# M705J.net
KiCad netlist of a schematic drawn in EAGLE
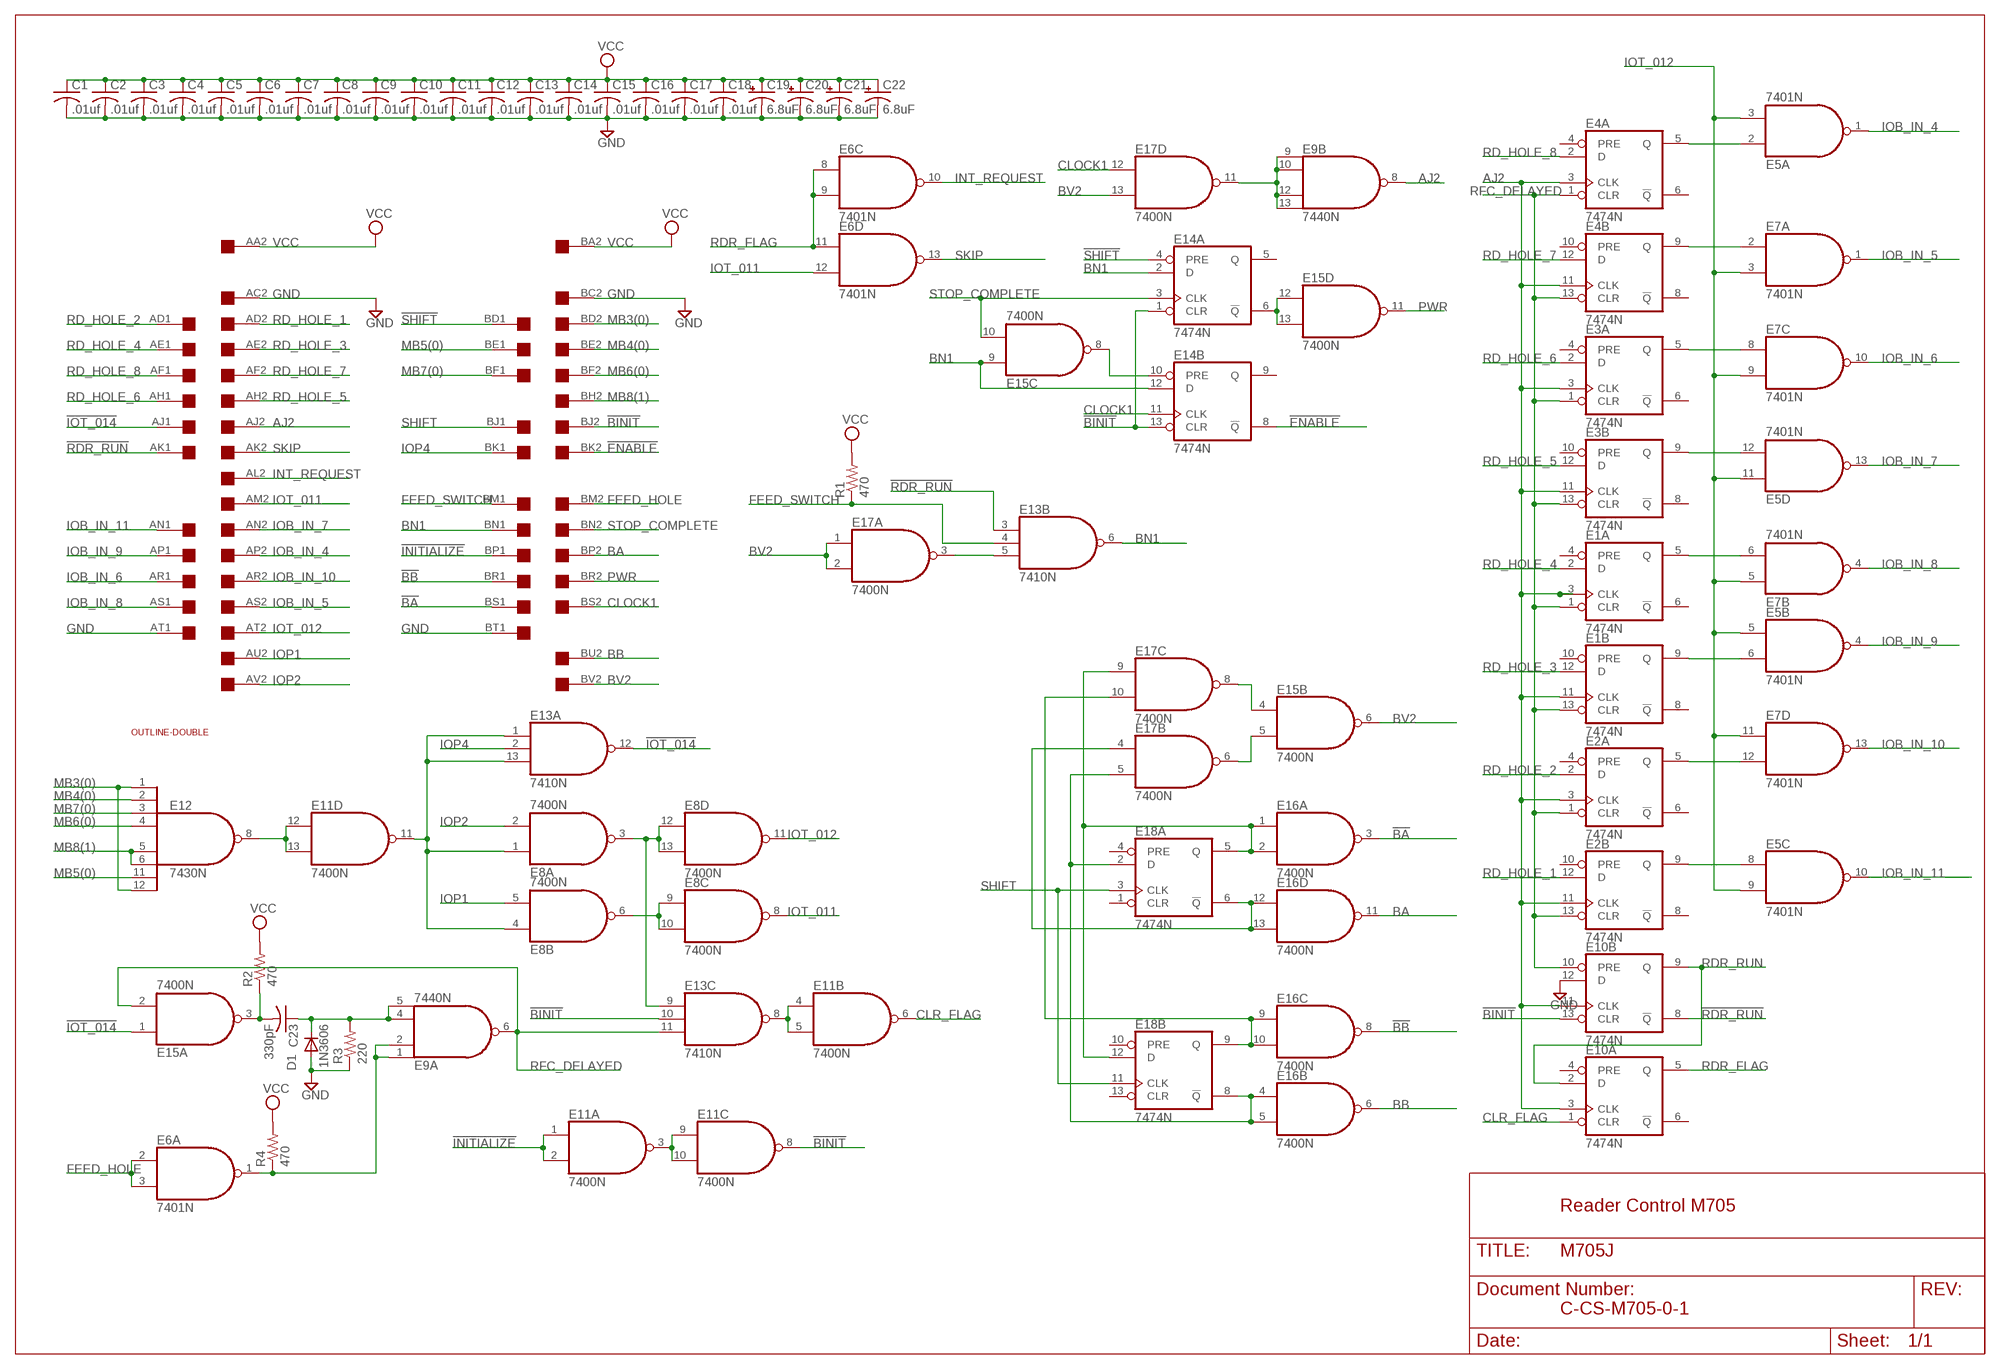
[diagram p0: schematic, sheet 1]

(export (version "E")
  (design (tool "Eeschema 10.0.6"))
  (components
    (comp (ref "C1")
      (value ".01uf")
      (footprint "eagle-import:C075-032X103")
      (libsource (lib "eagle-import") (part "C-US075-032X103"))
    )
    (comp (ref "C2")
      (value ".01uf")
      (footprint "eagle-import:C075-032X103")
      (libsource (lib "eagle-import") (part "C-US075-032X103"))
    )
    (comp (ref "C3")
      (value ".01uf")
      (footprint "eagle-import:C075-032X103")
      (libsource (lib "eagle-import") (part "C-US075-032X103"))
    )
    (comp (ref "C4")
      (value ".01uf")
      (footprint "eagle-import:C075-032X103")
      (libsource (lib "eagle-import") (part "C-US075-032X103"))
    )
    (comp (ref "C5")
      (value ".01uf")
      (footprint "eagle-import:C075-032X103")
      (libsource (lib "eagle-import") (part "C-US075-032X103"))
    )
    (comp (ref "C6")
      (value ".01uf")
      (footprint "eagle-import:C075-032X103")
      (libsource (lib "eagle-import") (part "C-US075-032X103"))
    )
    (comp (ref "C7")
      (value ".01uf")
      (footprint "eagle-import:C075-032X103")
      (libsource (lib "eagle-import") (part "C-US075-032X103"))
    )
    (comp (ref "C8")
      (value ".01uf")
      (footprint "eagle-import:C075-032X103")
      (libsource (lib "eagle-import") (part "C-US075-032X103"))
    )
    (comp (ref "C9")
      (value ".01uf")
      (footprint "eagle-import:C075-032X103")
      (libsource (lib "eagle-import") (part "C-US075-032X103"))
    )
    (comp (ref "C10")
      (value ".01uf")
      (footprint "eagle-import:C075-032X103")
      (libsource (lib "eagle-import") (part "C-US075-032X103"))
    )
    (comp (ref "C11")
      (value ".01uf")
      (footprint "eagle-import:C075-032X103")
      (libsource (lib "eagle-import") (part "C-US075-032X103"))
    )
    (comp (ref "C12")
      (value ".01uf")
      (footprint "eagle-import:C075-032X103")
      (libsource (lib "eagle-import") (part "C-US075-032X103"))
    )
    (comp (ref "C13")
      (value ".01uf")
      (footprint "eagle-import:C075-032X103")
      (libsource (lib "eagle-import") (part "C-US075-032X103"))
    )
    (comp (ref "C14")
      (value ".01uf")
      (footprint "eagle-import:C075-032X103")
      (libsource (lib "eagle-import") (part "C-US075-032X103"))
    )
    (comp (ref "C15")
      (value ".01uf")
      (footprint "eagle-import:C075-032X103")
      (libsource (lib "eagle-import") (part "C-US075-032X103"))
    )
    (comp (ref "C16")
      (value ".01uf")
      (footprint "eagle-import:C075-032X103")
      (libsource (lib "eagle-import") (part "C-US075-032X103"))
    )
    (comp (ref "C17")
      (value ".01uf")
      (footprint "eagle-import:C075-032X103")
      (libsource (lib "eagle-import") (part "C-US075-032X103"))
    )
    (comp (ref "C18")
      (value ".01uf")
      (footprint "eagle-import:C075-032X103")
      (libsource (lib "eagle-import") (part "C-US075-032X103"))
    )
    (comp (ref "C19")
      (value "6.8uF")
      (footprint "eagle-import:E12-8")
      (libsource (lib "eagle-import") (part "CPOL-USE20-8AXIAL"))
    )
    (comp (ref "C20")
      (value "6.8uF")
      (footprint "eagle-import:E12-8")
      (libsource (lib "eagle-import") (part "CPOL-USE20-8AXIAL"))
    )
    (comp (ref "C21")
      (value "6.8uF")
      (footprint "eagle-import:E12-8")
      (libsource (lib "eagle-import") (part "CPOL-USE20-8AXIAL"))
    )
    (comp (ref "C22")
      (value "6.8uF")
      (footprint "eagle-import:E12-8")
      (libsource (lib "eagle-import") (part "CPOL-USE20-8AXIAL"))
    )
    (comp (ref "C23")
      (value "330pF")
      (footprint "eagle-import:C075-032X103")
      (libsource (lib "eagle-import") (part "C-US075-032X103"))
    )
    (comp (ref "D1")
      (value "1N3606")
      (footprint "eagle-import:DO35-10")
      (libsource (lib "eagle-import") (part "1N4148DO35-10"))
    )
    (comp (ref "E1")
      (value "7474N")
      (footprint "eagle-import:DIL14")
      (libsource (lib "eagle-import") (part "7474NS"))
    )
    (comp (ref "E2")
      (value "7474N")
      (footprint "eagle-import:DIL14")
      (libsource (lib "eagle-import") (part "7474NS"))
    )
    (comp (ref "E3")
      (value "7474N")
      (footprint "eagle-import:DIL14")
      (libsource (lib "eagle-import") (part "7474NS"))
    )
    (comp (ref "E4")
      (value "7474N")
      (footprint "eagle-import:DIL14")
      (libsource (lib "eagle-import") (part "7474NS"))
    )
    (comp (ref "E5")
      (value "7401N")
      (footprint "eagle-import:DIL14")
      (libsource (lib "eagle-import") (part "7401NLS"))
    )
    (comp (ref "E6")
      (value "7401N")
      (footprint "eagle-import:DIL14")
      (libsource (lib "eagle-import") (part "7401NLS"))
    )
    (comp (ref "E7")
      (value "7401N")
      (footprint "eagle-import:DIL14")
      (libsource (lib "eagle-import") (part "7401NLS"))
    )
    (comp (ref "E8")
      (value "7400N")
      (footprint "eagle-import:DIL14")
      (libsource (lib "eagle-import") (part "7400N"))
    )
    (comp (ref "E9")
      (value "7440N")
      (footprint "eagle-import:DIL14")
      (libsource (lib "eagle-import") (part "7420NS"))
    )
    (comp (ref "E10")
      (value "7474N")
      (footprint "eagle-import:DIL14")
      (libsource (lib "eagle-import") (part "7474NS"))
    )
    (comp (ref "E11")
      (value "7400N")
      (footprint "eagle-import:DIL14")
      (libsource (lib "eagle-import") (part "7400N"))
    )
    (comp (ref "E12")
      (value "7430N")
      (footprint "eagle-import:DIL14")
      (libsource (lib "eagle-import") (part "7430N"))
    )
    (comp (ref "E13")
      (value "7410N")
      (footprint "eagle-import:DIL14")
      (libsource (lib "eagle-import") (part "7410N"))
    )
    (comp (ref "E14")
      (value "7474N")
      (footprint "eagle-import:DIL14")
      (libsource (lib "eagle-import") (part "7474NS"))
    )
    (comp (ref "E15")
      (value "7400N")
      (footprint "eagle-import:DIL14")
      (libsource (lib "eagle-import") (part "7400N"))
    )
    (comp (ref "E16")
      (value "7400N")
      (footprint "eagle-import:DIL14")
      (libsource (lib "eagle-import") (part "7400N"))
    )
    (comp (ref "E17")
      (value "7400N")
      (footprint "eagle-import:DIL14")
      (libsource (lib "eagle-import") (part "7400N"))
    )
    (comp (ref "E18")
      (value "7474N")
      (footprint "eagle-import:DIL14")
      (libsource (lib "eagle-import") (part "7474NS"))
    )
    (comp (ref "R1")
      (value "470")
      (footprint "eagle-import:0207_10")
      (libsource (lib "eagle-import") (part "R-US_0207/10"))
    )
    (comp (ref "R2")
      (value "470")
      (footprint "eagle-import:0207_10")
      (libsource (lib "eagle-import") (part "R-US_0207/10"))
    )
    (comp (ref "R3")
      (value "220")
      (footprint "eagle-import:0207_10")
      (libsource (lib "eagle-import") (part "R-US_0207/10"))
    )
    (comp (ref "R4")
      (value "470")
      (footprint "eagle-import:0207_10")
      (libsource (lib "eagle-import") (part "R-US_0207/10"))
    )
    (comp (ref "U$5")
      (value "DOUBLE")
      (footprint "eagle-import:EDGE-CON4")
      (libsource (lib "eagle-import") (part "DOUBLE"))
    )
    (comp (ref "U$6")
      (value "OUTLINE-DOUBLE")
      (footprint "eagle-import:DOUBLE")
      (libsource (lib "eagle-import") (part "OUTLINE-DOUBLE"))
    )
  )
  (nets
    (net (code "1") (name "/AJ2") (class "Default")
      (node (ref "E1") (pin "11") (pinfunction "CLK_11") (pintype "input"))
      (node (ref "E1") (pin "3") (pinfunction "CLK_3") (pintype "input"))
      (node (ref "E10") (pin "11") (pinfunction "CLK_11") (pintype "input"))
      (node (ref "E10") (pin "3") (pinfunction "CLK_3") (pintype "input"))
      (node (ref "E2") (pin "11") (pinfunction "CLK_11") (pintype "input"))
      (node (ref "E2") (pin "3") (pinfunction "CLK_3") (pintype "input"))
      (node (ref "E3") (pin "11") (pinfunction "CLK_11") (pintype "input"))
      (node (ref "E3") (pin "3") (pinfunction "CLK_3") (pintype "input"))
      (node (ref "E4") (pin "11") (pinfunction "CLK_11") (pintype "input"))
      (node (ref "E4") (pin "3") (pinfunction "CLK_3") (pintype "input"))
      (node (ref "E9") (pin "8") (pinfunction "O_8") (pintype "output"))
      (node (ref "U$5") (pin "AJ2") (pinfunction "1_AJ2") (pintype "bidirectional"))
    )
    (net (code "2") (name "/BA") (class "Default")
      (node (ref "E16") (pin "11") (pinfunction "O_11") (pintype "output"))
      (node (ref "U$5") (pin "BP2") (pinfunction "1_BP2") (pintype "bidirectional"))
    )
    (net (code "3") (name "/BB") (class "Default")
      (node (ref "E16") (pin "6") (pinfunction "O_6") (pintype "output"))
      (node (ref "U$5") (pin "BU2") (pinfunction "1_BU2") (pintype "bidirectional"))
    )
    (net (code "4") (name "/BN1") (class "Default")
      (node (ref "E13") (pin "6") (pinfunction "O_6") (pintype "output"))
      (node (ref "E14") (pin "12") (pinfunction "D_12") (pintype "input"))
      (node (ref "E14") (pin "2") (pinfunction "D_2") (pintype "input"))
      (node (ref "E15") (pin "9") (pinfunction "I0_9") (pintype "input"))
      (node (ref "U$5") (pin "BN1") (pinfunction "1_BN1") (pintype "bidirectional"))
    )
    (net (code "5") (name "/BV2") (class "Default")
      (node (ref "E15") (pin "6") (pinfunction "O_6") (pintype "output"))
      (node (ref "E17") (pin "1") (pinfunction "I0_1") (pintype "input"))
      (node (ref "E17") (pin "13") (pinfunction "I1_13") (pintype "input"))
      (node (ref "E17") (pin "2") (pinfunction "I1_2") (pintype "input"))
      (node (ref "U$5") (pin "BV2") (pinfunction "1_BV2") (pintype "bidirectional"))
    )
    (net (code "6") (name "/CLOCK1") (class "Default")
      (node (ref "E14") (pin "11") (pinfunction "CLK_11") (pintype "input"))
      (node (ref "E17") (pin "12") (pinfunction "I0_12") (pintype "input"))
      (node (ref "U$5") (pin "BS2") (pinfunction "1_BS2") (pintype "bidirectional"))
    )
    (net (code "7") (name "/CLR_FLAG") (class "Default")
      (node (ref "E10") (pin "1") (pinfunction "CLR_1") (pintype "input"))
      (node (ref "E11") (pin "6") (pinfunction "O_6") (pintype "output"))
    )
    (net (code "8") (name "/FEED_HOLE") (class "Default")
      (node (ref "E6") (pin "2") (pinfunction "I0_2") (pintype "input"))
      (node (ref "E6") (pin "3") (pinfunction "I1_3") (pintype "input"))
      (node (ref "U$5") (pin "BM2") (pinfunction "1_BM2") (pintype "bidirectional"))
    )
    (net (code "9") (name "/FEED_SWITCH") (class "Default")
      (node (ref "E13") (pin "4") (pinfunction "I1_4") (pintype "input"))
      (node (ref "R1") (pin "1") (pinfunction "1_1") (pintype "passive"))
      (node (ref "U$5") (pin "BM1") (pinfunction "1_BM1") (pintype "bidirectional"))
    )
    (net (code "10") (name "/INT_REQUEST") (class "Default")
      (node (ref "E6") (pin "10") (pinfunction "O_10") (pintype "open_collector"))
      (node (ref "U$5") (pin "AL2") (pinfunction "1_AL2") (pintype "bidirectional"))
    )
    (net (code "11") (name "/IOB_IN_4") (class "Default")
      (node (ref "E5") (pin "1") (pinfunction "O_1") (pintype "open_collector"))
      (node (ref "U$5") (pin "AP2") (pinfunction "1_AP2") (pintype "bidirectional"))
    )
    (net (code "12") (name "/IOB_IN_5") (class "Default")
      (node (ref "E7") (pin "1") (pinfunction "O_1") (pintype "open_collector"))
      (node (ref "U$5") (pin "AS2") (pinfunction "1_AS2") (pintype "bidirectional"))
    )
    (net (code "13") (name "/IOB_IN_6") (class "Default")
      (node (ref "E7") (pin "10") (pinfunction "O_10") (pintype "open_collector"))
      (node (ref "U$5") (pin "AR1") (pinfunction "1_AR1") (pintype "bidirectional"))
    )
    (net (code "14") (name "/IOB_IN_7") (class "Default")
      (node (ref "E5") (pin "13") (pinfunction "O_13") (pintype "open_collector"))
      (node (ref "U$5") (pin "AN2") (pinfunction "1_AN2") (pintype "bidirectional"))
    )
    (net (code "15") (name "/IOB_IN_8") (class "Default")
      (node (ref "E7") (pin "4") (pinfunction "O_4") (pintype "open_collector"))
      (node (ref "U$5") (pin "AS1") (pinfunction "1_AS1") (pintype "bidirectional"))
    )
    (net (code "16") (name "/IOB_IN_9") (class "Default")
      (node (ref "E5") (pin "4") (pinfunction "O_4") (pintype "open_collector"))
      (node (ref "U$5") (pin "AP1") (pinfunction "1_AP1") (pintype "bidirectional"))
    )
    (net (code "17") (name "/IOB_IN_10") (class "Default")
      (node (ref "E7") (pin "13") (pinfunction "O_13") (pintype "open_collector"))
      (node (ref "U$5") (pin "AR2") (pinfunction "1_AR2") (pintype "bidirectional"))
    )
    (net (code "18") (name "/IOB_IN_11") (class "Default")
      (node (ref "E5") (pin "10") (pinfunction "O_10") (pintype "open_collector"))
      (node (ref "U$5") (pin "AN1") (pinfunction "1_AN1") (pintype "bidirectional"))
    )
    (net (code "19") (name "/IOP1") (class "Default")
      (node (ref "E8") (pin "5") (pinfunction "I1_5") (pintype "input"))
      (node (ref "U$5") (pin "AU2") (pinfunction "1_AU2") (pintype "bidirectional"))
    )
    (net (code "20") (name "/IOP2") (class "Default")
      (node (ref "E8") (pin "2") (pinfunction "I1_2") (pintype "input"))
      (node (ref "U$5") (pin "AV2") (pinfunction "1_AV2") (pintype "bidirectional"))
    )
    (net (code "21") (name "/IOP4") (class "Default")
      (node (ref "E13") (pin "2") (pinfunction "I1_2") (pintype "input"))
      (node (ref "U$5") (pin "BK1") (pinfunction "1_BK1") (pintype "bidirectional"))
    )
    (net (code "22") (name "/IOT_011") (class "Default")
      (node (ref "E6") (pin "12") (pinfunction "I1_12") (pintype "input"))
      (node (ref "E8") (pin "8") (pinfunction "O_8") (pintype "output"))
      (node (ref "U$5") (pin "AM2") (pinfunction "1_AM2") (pintype "bidirectional"))
    )
    (net (code "23") (name "/IOT_012") (class "Default")
      (node (ref "E5") (pin "11") (pinfunction "I0_11") (pintype "input"))
      (node (ref "E5") (pin "3") (pinfunction "I1_3") (pintype "input"))
      (node (ref "E5") (pin "5") (pinfunction "I0_5") (pintype "input"))
      (node (ref "E5") (pin "9") (pinfunction "I1_9") (pintype "input"))
      (node (ref "E7") (pin "11") (pinfunction "I0_11") (pintype "input"))
      (node (ref "E7") (pin "3") (pinfunction "I1_3") (pintype "input"))
      (node (ref "E7") (pin "5") (pinfunction "I0_5") (pintype "input"))
      (node (ref "E7") (pin "9") (pinfunction "I1_9") (pintype "input"))
      (node (ref "E8") (pin "11") (pinfunction "O_11") (pintype "output"))
      (node (ref "U$5") (pin "AT2") (pinfunction "1_AT2") (pintype "bidirectional"))
    )
    (net (code "24") (name "/MB3(0)") (class "Default")
      (node (ref "E12") (pin "1") (pinfunction "I0_1") (pintype "input"))
      (node (ref "E12") (pin "12") (pinfunction "I7_12") (pintype "input"))
      (node (ref "U$5") (pin "BD2") (pinfunction "1_BD2") (pintype "bidirectional"))
    )
    (net (code "25") (name "/MB4(0)") (class "Default")
      (node (ref "E12") (pin "2") (pinfunction "I1_2") (pintype "input"))
      (node (ref "U$5") (pin "BE2") (pinfunction "1_BE2") (pintype "bidirectional"))
    )
    (net (code "26") (name "/MB5(0)") (class "Default")
      (node (ref "E12") (pin "11") (pinfunction "I6_11") (pintype "input"))
      (node (ref "U$5") (pin "BE1") (pinfunction "1_BE1") (pintype "bidirectional"))
    )
    (net (code "27") (name "/MB6(0)") (class "Default")
      (node (ref "E12") (pin "4") (pinfunction "I3_4") (pintype "input"))
      (node (ref "U$5") (pin "BF2") (pinfunction "1_BF2") (pintype "bidirectional"))
    )
    (net (code "28") (name "/MB7(0)") (class "Default")
      (node (ref "E12") (pin "3") (pinfunction "I2_3") (pintype "input"))
      (node (ref "U$5") (pin "BF1") (pinfunction "1_BF1") (pintype "bidirectional"))
    )
    (net (code "29") (name "/MB8(1)") (class "Default")
      (node (ref "E12") (pin "5") (pinfunction "I4_5") (pintype "input"))
      (node (ref "E12") (pin "6") (pinfunction "I5_6") (pintype "input"))
      (node (ref "U$5") (pin "BH2") (pinfunction "1_BH2") (pintype "bidirectional"))
    )
    (net (code "30") (name "/PWR") (class "Default")
      (node (ref "E15") (pin "11") (pinfunction "O_11") (pintype "output"))
      (node (ref "U$5") (pin "BR2") (pinfunction "1_BR2") (pintype "bidirectional"))
    )
    (net (code "31") (name "/RDR_FLAG") (class "Default")
      (node (ref "E10") (pin "5") (pinfunction "Q_5") (pintype "output"))
      (node (ref "E6") (pin "11") (pinfunction "I0_11") (pintype "input"))
      (node (ref "E6") (pin "8") (pinfunction "I0_8") (pintype "input"))
      (node (ref "E6") (pin "9") (pinfunction "I1_9") (pintype "input"))
    )
    (net (code "32") (name "/RDR_RUN") (class "Default")
      (node (ref "E10") (pin "2") (pinfunction "D_2") (pintype "input"))
      (node (ref "E10") (pin "9") (pinfunction "Q_9") (pintype "output"))
    )
    (net (code "33") (name "/RD_HOLE_1") (class "Default")
      (node (ref "E2") (pin "12") (pinfunction "D_12") (pintype "input"))
      (node (ref "U$5") (pin "AD2") (pinfunction "1_AD2") (pintype "bidirectional"))
    )
    (net (code "34") (name "/RD_HOLE_2") (class "Default")
      (node (ref "E2") (pin "2") (pinfunction "D_2") (pintype "input"))
      (node (ref "U$5") (pin "AD1") (pinfunction "1_AD1") (pintype "bidirectional"))
    )
    (net (code "35") (name "/RD_HOLE_3") (class "Default")
      (node (ref "E1") (pin "12") (pinfunction "D_12") (pintype "input"))
      (node (ref "U$5") (pin "AE2") (pinfunction "1_AE2") (pintype "bidirectional"))
    )
    (net (code "36") (name "/RD_HOLE_4") (class "Default")
      (node (ref "E1") (pin "2") (pinfunction "D_2") (pintype "input"))
      (node (ref "U$5") (pin "AE1") (pinfunction "1_AE1") (pintype "bidirectional"))
    )
    (net (code "37") (name "/RD_HOLE_5") (class "Default")
      (node (ref "E3") (pin "12") (pinfunction "D_12") (pintype "input"))
      (node (ref "U$5") (pin "AH2") (pinfunction "1_AH2") (pintype "bidirectional"))
    )
    (net (code "38") (name "/RD_HOLE_6") (class "Default")
      (node (ref "E3") (pin "2") (pinfunction "D_2") (pintype "input"))
      (node (ref "U$5") (pin "AH1") (pinfunction "1_AH1") (pintype "bidirectional"))
    )
    (net (code "39") (name "/RD_HOLE_7") (class "Default")
      (node (ref "E4") (pin "12") (pinfunction "D_12") (pintype "input"))
      (node (ref "U$5") (pin "AF2") (pinfunction "1_AF2") (pintype "bidirectional"))
    )
    (net (code "40") (name "/RD_HOLE_8") (class "Default")
      (node (ref "E4") (pin "2") (pinfunction "D_2") (pintype "input"))
      (node (ref "U$5") (pin "AF1") (pinfunction "1_AF1") (pintype "bidirectional"))
    )
    (net (code "41") (name "/RFC_DELAYED") (class "Default")
      (node (ref "E1") (pin "1") (pinfunction "CLR_1") (pintype "input"))
      (node (ref "E1") (pin "13") (pinfunction "CLR_13") (pintype "input"))
      (node (ref "E10") (pin "10") (pinfunction "PRE_10") (pintype "input"))
      (node (ref "E13") (pin "11") (pinfunction "I2_11") (pintype "input"))
      (node (ref "E15") (pin "2") (pinfunction "I1_2") (pintype "input"))
      (node (ref "E2") (pin "1") (pinfunction "CLR_1") (pintype "input"))
      (node (ref "E2") (pin "13") (pinfunction "CLR_13") (pintype "input"))
      (node (ref "E3") (pin "1") (pinfunction "CLR_1") (pintype "input"))
      (node (ref "E3") (pin "13") (pinfunction "CLR_13") (pintype "input"))
      (node (ref "E4") (pin "1") (pinfunction "CLR_1") (pintype "input"))
      (node (ref "E4") (pin "13") (pinfunction "CLR_13") (pintype "input"))
      (node (ref "E9") (pin "6") (pinfunction "O_6") (pintype "output"))
    )
    (net (code "42") (name "/SHIFT") (class "Default")
      (node (ref "E18") (pin "11") (pinfunction "CLK_11") (pintype "input"))
      (node (ref "E18") (pin "3") (pinfunction "CLK_3") (pintype "input"))
      (node (ref "U$5") (pin "BJ1") (pinfunction "1_BJ1") (pintype "bidirectional"))
    )
    (net (code "43") (name "/SKIP") (class "Default")
      (node (ref "E6") (pin "13") (pinfunction "O_13") (pintype "open_collector"))
      (node (ref "U$5") (pin "AK2") (pinfunction "1_AK2") (pintype "bidirectional"))
    )
    (net (code "44") (name "/STOP_COMPLETE") (class "Default")
      (node (ref "E14") (pin "3") (pinfunction "CLK_3") (pintype "input"))
      (node (ref "E15") (pin "10") (pinfunction "I1_10") (pintype "input"))
      (node (ref "U$5") (pin "BN2") (pinfunction "1_BN2") (pintype "bidirectional"))
    )
    (net (code "45") (name "/~{BA}") (class "Default")
      (node (ref "E16") (pin "3") (pinfunction "O_3") (pintype "output"))
      (node (ref "U$5") (pin "BS1") (pinfunction "1_BS1") (pintype "bidirectional"))
    )
    (net (code "46") (name "/~{BB}") (class "Default")
      (node (ref "E16") (pin "8") (pinfunction "O_8") (pintype "output"))
      (node (ref "U$5") (pin "BR1") (pinfunction "1_BR1") (pintype "bidirectional"))
    )
    (net (code "47") (name "/~{BINIT}") (class "Default")
      (node (ref "E10") (pin "13") (pinfunction "CLR_13") (pintype "input"))
      (node (ref "E11") (pin "8") (pinfunction "O_8") (pintype "output"))
      (node (ref "E13") (pin "10") (pinfunction "I1_10") (pintype "input"))
      (node (ref "E14") (pin "1") (pinfunction "CLR_1") (pintype "input"))
      (node (ref "E14") (pin "13") (pinfunction "CLR_13") (pintype "input"))
      (node (ref "U$5") (pin "BJ2") (pinfunction "1_BJ2") (pintype "bidirectional"))
    )
    (net (code "48") (name "/~{ENABLE}") (class "Default")
      (node (ref "E14") (pin "8") (pinfunction "~{Q}_8") (pintype "output"))
      (node (ref "U$5") (pin "BK2") (pinfunction "1_BK2") (pintype "bidirectional"))
    )
    (net (code "49") (name "/~{INITIALIZE}") (class "Default")
      (node (ref "E11") (pin "1") (pinfunction "I0_1") (pintype "input"))
      (node (ref "E11") (pin "2") (pinfunction "I1_2") (pintype "input"))
      (node (ref "U$5") (pin "BP1") (pinfunction "1_BP1") (pintype "bidirectional"))
    )
    (net (code "50") (name "/~{IOT_014}") (class "Default")
      (node (ref "E13") (pin "12") (pinfunction "O_12") (pintype "output"))
      (node (ref "E15") (pin "1") (pinfunction "I0_1") (pintype "input"))
      (node (ref "U$5") (pin "AJ1") (pinfunction "1_AJ1") (pintype "bidirectional"))
    )
    (net (code "51") (name "/~{RDR_RUN}") (class "Default")
      (node (ref "E10") (pin "8") (pinfunction "~{Q}_8") (pintype "output"))
      (node (ref "E13") (pin "3") (pinfunction "I0_3") (pintype "input"))
      (node (ref "U$5") (pin "AK1") (pinfunction "1_AK1") (pintype "bidirectional"))
    )
    (net (code "52") (name "/~{SHIFT}") (class "Default")
      (node (ref "E14") (pin "4") (pinfunction "PRE_4") (pintype "input"))
      (node (ref "U$5") (pin "BD1") (pinfunction "1_BD1") (pintype "bidirectional"))
    )
    (net (code "53") (name "GND") (class "Default")
      (node (ref "C1") (pin "2") (pinfunction "2_2") (pintype "passive"))
      (node (ref "C10") (pin "2") (pinfunction "2_2") (pintype "passive"))
      (node (ref "C11") (pin "2") (pinfunction "2_2") (pintype "passive"))
      (node (ref "C12") (pin "2") (pinfunction "2_2") (pintype "passive"))
      (node (ref "C13") (pin "2") (pinfunction "2_2") (pintype "passive"))
      (node (ref "C14") (pin "2") (pinfunction "2_2") (pintype "passive"))
      (node (ref "C15") (pin "2") (pinfunction "2_2") (pintype "passive"))
      (node (ref "C16") (pin "2") (pinfunction "2_2") (pintype "passive"))
      (node (ref "C17") (pin "2") (pinfunction "2_2") (pintype "passive"))
      (node (ref "C18") (pin "2") (pinfunction "2_2") (pintype "passive"))
      (node (ref "C19") (pin "-") (pinfunction "-_-") (pintype "passive"))
      (node (ref "C2") (pin "2") (pinfunction "2_2") (pintype "passive"))
      (node (ref "C20") (pin "-") (pinfunction "-_-") (pintype "passive"))
      (node (ref "C21") (pin "-") (pinfunction "-_-") (pintype "passive"))
      (node (ref "C22") (pin "-") (pinfunction "-_-") (pintype "passive"))
      (node (ref "C3") (pin "2") (pinfunction "2_2") (pintype "passive"))
      (node (ref "C4") (pin "2") (pinfunction "2_2") (pintype "passive"))
      (node (ref "C5") (pin "2") (pinfunction "2_2") (pintype "passive"))
      (node (ref "C6") (pin "2") (pinfunction "2_2") (pintype "passive"))
      (node (ref "C7") (pin "2") (pinfunction "2_2") (pintype "passive"))
      (node (ref "C8") (pin "2") (pinfunction "2_2") (pintype "passive"))
      (node (ref "C9") (pin "2") (pinfunction "2_2") (pintype "passive"))
      (node (ref "D1") (pin "A") (pinfunction "A_A") (pintype "passive"))
      (node (ref "E10") (pin "12") (pinfunction "D_12") (pintype "input"))
      (node (ref "R3") (pin "1") (pinfunction "1_1") (pintype "passive"))
      (node (ref "U$5") (pin "AC2") (pinfunction "1_AC2") (pintype "bidirectional"))
      (node (ref "U$5") (pin "AT1") (pinfunction "1_AT1") (pintype "bidirectional"))
      (node (ref "U$5") (pin "BC2") (pinfunction "1_BC2") (pintype "bidirectional"))
      (node (ref "U$5") (pin "BT1") (pinfunction "1_BT1") (pintype "bidirectional"))
    )
    (net (code "54") (name "Net-(E1A-Q)") (class "Default")
      (node (ref "E1") (pin "5") (pinfunction "Q_5") (pintype "output"))
      (node (ref "E7") (pin "6") (pinfunction "I1_6") (pintype "input"))
    )
    (net (code "55") (name "Net-(E1B-Q)") (class "Default")
      (node (ref "E1") (pin "9") (pinfunction "Q_9") (pintype "output"))
      (node (ref "E5") (pin "6") (pinfunction "I1_6") (pintype "input"))
    )
    (net (code "56") (name "Net-(E2A-Q)") (class "Default")
      (node (ref "E2") (pin "5") (pinfunction "Q_5") (pintype "output"))
      (node (ref "E7") (pin "12") (pinfunction "I1_12") (pintype "input"))
    )
    (net (code "57") (name "Net-(E2B-Q)") (class "Default")
      (node (ref "E2") (pin "9") (pinfunction "Q_9") (pintype "output"))
      (node (ref "E5") (pin "8") (pinfunction "I0_8") (pintype "input"))
    )
    (net (code "58") (name "Net-(E3A-Q)") (class "Default")
      (node (ref "E3") (pin "5") (pinfunction "Q_5") (pintype "output"))
      (node (ref "E7") (pin "8") (pinfunction "I0_8") (pintype "input"))
    )
    (net (code "59") (name "Net-(E3B-Q)") (class "Default")
      (node (ref "E3") (pin "9") (pinfunction "Q_9") (pintype "output"))
      (node (ref "E5") (pin "12") (pinfunction "I1_12") (pintype "input"))
    )
    (net (code "60") (name "Net-(E4A-Q)") (class "Default")
      (node (ref "E4") (pin "5") (pinfunction "Q_5") (pintype "output"))
      (node (ref "E5") (pin "2") (pinfunction "I0_2") (pintype "input"))
    )
    (net (code "61") (name "Net-(E4B-Q)") (class "Default")
      (node (ref "E4") (pin "9") (pinfunction "Q_9") (pintype "output"))
      (node (ref "E7") (pin "2") (pinfunction "I0_2") (pintype "input"))
    )
    (net (code "62") (name "Net-(E6A-O)") (class "Default")
      (node (ref "E6") (pin "1") (pinfunction "O_1") (pintype "open_collector"))
      (node (ref "E9") (pin "1") (pinfunction "I0_1") (pintype "input"))
      (node (ref "E9") (pin "2") (pinfunction "I1_2") (pintype "input"))
      (node (ref "R4") (pin "1") (pinfunction "1_1") (pintype "passive"))
    )
    (net (code "63") (name "Net-(E8B-O)") (class "Default")
      (node (ref "E8") (pin "10") (pinfunction "I1_10") (pintype "input"))
      (node (ref "E8") (pin "6") (pinfunction "O_6") (pintype "output"))
      (node (ref "E8") (pin "9") (pinfunction "I0_9") (pintype "input"))
    )
    (net (code "64") (name "Net-(E9A-I2)") (class "Default")
      (node (ref "C23") (pin "1") (pinfunction "1_1") (pintype "passive"))
      (node (ref "D1") (pin "C") (pinfunction "C_C") (pintype "passive"))
      (node (ref "E9") (pin "4") (pinfunction "I2_4") (pintype "input"))
      (node (ref "E9") (pin "5") (pinfunction "I3_5") (pintype "input"))
      (node (ref "R3") (pin "2") (pinfunction "2_2") (pintype "passive"))
    )
    (net (code "65") (name "Net-(E11A-O)") (class "Default")
      (node (ref "E11") (pin "10") (pinfunction "I1_10") (pintype "input"))
      (node (ref "E11") (pin "3") (pinfunction "O_3") (pintype "output"))
      (node (ref "E11") (pin "9") (pinfunction "I0_9") (pintype "input"))
    )
    (net (code "66") (name "Net-(E11B-I0)") (class "Default")
      (node (ref "E11") (pin "4") (pinfunction "I0_4") (pintype "input"))
      (node (ref "E11") (pin "5") (pinfunction "I1_5") (pintype "input"))
      (node (ref "E13") (pin "8") (pinfunction "O_8") (pintype "output"))
    )
    (net (code "67") (name "Net-(E11D-I0)") (class "Default")
      (node (ref "E11") (pin "12") (pinfunction "I0_12") (pintype "input"))
      (node (ref "E11") (pin "13") (pinfunction "I1_13") (pintype "input"))
      (node (ref "E12") (pin "8") (pinfunction "O_8") (pintype "output"))
    )
    (net (code "68") (name "Net-(E11D-O)") (class "Default")
      (node (ref "E11") (pin "11") (pinfunction "O_11") (pintype "output"))
      (node (ref "E13") (pin "1") (pinfunction "I0_1") (pintype "input"))
      (node (ref "E13") (pin "13") (pinfunction "I2_13") (pintype "input"))
      (node (ref "E8") (pin "1") (pinfunction "I0_1") (pintype "input"))
      (node (ref "E8") (pin "4") (pinfunction "I0_4") (pintype "input"))
    )
    (net (code "69") (name "Net-(E13B-I2)") (class "Default")
      (node (ref "E13") (pin "5") (pinfunction "I2_5") (pintype "input"))
      (node (ref "E17") (pin "3") (pinfunction "O_3") (pintype "output"))
    )
    (net (code "70") (name "Net-(E13C-I0)") (class "Default")
      (node (ref "E13") (pin "9") (pinfunction "I0_9") (pintype "input"))
      (node (ref "E8") (pin "12") (pinfunction "I0_12") (pintype "input"))
      (node (ref "E8") (pin "13") (pinfunction "I1_13") (pintype "input"))
      (node (ref "E8") (pin "3") (pinfunction "O_3") (pintype "output"))
    )
    (net (code "71") (name "Net-(E14A-~{Q})") (class "Default")
      (node (ref "E14") (pin "6") (pinfunction "~{Q}_6") (pintype "output"))
      (node (ref "E15") (pin "12") (pinfunction "I0_12") (pintype "input"))
      (node (ref "E15") (pin "13") (pinfunction "I1_13") (pintype "input"))
    )
    (net (code "72") (name "Net-(E14B-PRE)") (class "Default")
      (node (ref "E14") (pin "10") (pinfunction "PRE_10") (pintype "input"))
      (node (ref "E15") (pin "8") (pinfunction "O_8") (pintype "output"))
    )
    (net (code "73") (name "Net-(E15A-O)") (class "Default")
      (node (ref "C23") (pin "2") (pinfunction "2_2") (pintype "passive"))
      (node (ref "E15") (pin "3") (pinfunction "O_3") (pintype "output"))
      (node (ref "R2") (pin "1") (pinfunction "1_1") (pintype "passive"))
    )
    (net (code "74") (name "Net-(E15B-I0)") (class "Default")
      (node (ref "E15") (pin "4") (pinfunction "I0_4") (pintype "input"))
      (node (ref "E17") (pin "8") (pinfunction "O_8") (pintype "output"))
    )
    (net (code "75") (name "Net-(E15B-I1)") (class "Default")
      (node (ref "E15") (pin "5") (pinfunction "I1_5") (pintype "input"))
      (node (ref "E17") (pin "6") (pinfunction "O_6") (pintype "output"))
    )
    (net (code "76") (name "Net-(E16A-I0)") (class "Default")
      (node (ref "E16") (pin "1") (pinfunction "I0_1") (pintype "input"))
      (node (ref "E16") (pin "2") (pinfunction "I1_2") (pintype "input"))
      (node (ref "E17") (pin "9") (pinfunction "I0_9") (pintype "input"))
      (node (ref "E18") (pin "12") (pinfunction "D_12") (pintype "input"))
      (node (ref "E18") (pin "5") (pinfunction "Q_5") (pintype "output"))
    )
    (net (code "77") (name "Net-(E16B-I0)") (class "Default")
      (node (ref "E16") (pin "4") (pinfunction "I0_4") (pintype "input"))
      (node (ref "E16") (pin "5") (pinfunction "I1_5") (pintype "input"))
      (node (ref "E17") (pin "5") (pinfunction "I1_5") (pintype "input"))
      (node (ref "E18") (pin "2") (pinfunction "D_2") (pintype "input"))
      (node (ref "E18") (pin "8") (pinfunction "~{Q}_8") (pintype "output"))
    )
    (net (code "78") (name "Net-(E16C-I0)") (class "Default")
      (node (ref "E16") (pin "10") (pinfunction "I1_10") (pintype "input"))
      (node (ref "E16") (pin "9") (pinfunction "I0_9") (pintype "input"))
      (node (ref "E17") (pin "10") (pinfunction "I1_10") (pintype "input"))
      (node (ref "E18") (pin "9") (pinfunction "Q_9") (pintype "output"))
    )
    (net (code "79") (name "Net-(E16D-I0)") (class "Default")
      (node (ref "E16") (pin "12") (pinfunction "I0_12") (pintype "input"))
      (node (ref "E16") (pin "13") (pinfunction "I1_13") (pintype "input"))
      (node (ref "E17") (pin "4") (pinfunction "I0_4") (pintype "input"))
      (node (ref "E18") (pin "6") (pinfunction "~{Q}_6") (pintype "output"))
    )
    (net (code "80") (name "Net-(E17D-O)") (class "Default")
      (node (ref "E17") (pin "11") (pinfunction "O_11") (pintype "output"))
      (node (ref "E9") (pin "10") (pinfunction "I1_10") (pintype "input"))
      (node (ref "E9") (pin "12") (pinfunction "I2_12") (pintype "input"))
      (node (ref "E9") (pin "13") (pinfunction "I3_13") (pintype "input"))
      (node (ref "E9") (pin "9") (pinfunction "I0_9") (pintype "input"))
    )
    (net (code "81") (name "VCC") (class "Default")
      (node (ref "C1") (pin "1") (pinfunction "1_1") (pintype "passive"))
      (node (ref "C10") (pin "1") (pinfunction "1_1") (pintype "passive"))
      (node (ref "C11") (pin "1") (pinfunction "1_1") (pintype "passive"))
      (node (ref "C12") (pin "1") (pinfunction "1_1") (pintype "passive"))
      (node (ref "C13") (pin "1") (pinfunction "1_1") (pintype "passive"))
      (node (ref "C14") (pin "1") (pinfunction "1_1") (pintype "passive"))
      (node (ref "C15") (pin "1") (pinfunction "1_1") (pintype "passive"))
      (node (ref "C16") (pin "1") (pinfunction "1_1") (pintype "passive"))
      (node (ref "C17") (pin "1") (pinfunction "1_1") (pintype "passive"))
      (node (ref "C18") (pin "1") (pinfunction "1_1") (pintype "passive"))
      (node (ref "C19") (pin "+") (pinfunction "+_+") (pintype "passive"))
      (node (ref "C2") (pin "1") (pinfunction "1_1") (pintype "passive"))
      (node (ref "C20") (pin "+") (pinfunction "+_+") (pintype "passive"))
      (node (ref "C21") (pin "+") (pinfunction "+_+") (pintype "passive"))
      (node (ref "C22") (pin "+") (pinfunction "+_+") (pintype "passive"))
      (node (ref "C3") (pin "1") (pinfunction "1_1") (pintype "passive"))
      (node (ref "C4") (pin "1") (pinfunction "1_1") (pintype "passive"))
      (node (ref "C5") (pin "1") (pinfunction "1_1") (pintype "passive"))
      (node (ref "C6") (pin "1") (pinfunction "1_1") (pintype "passive"))
      (node (ref "C7") (pin "1") (pinfunction "1_1") (pintype "passive"))
      (node (ref "C8") (pin "1") (pinfunction "1_1") (pintype "passive"))
      (node (ref "C9") (pin "1") (pinfunction "1_1") (pintype "passive"))
      (node (ref "R1") (pin "2") (pinfunction "2_2") (pintype "passive"))
      (node (ref "R2") (pin "2") (pinfunction "2_2") (pintype "passive"))
      (node (ref "R4") (pin "2") (pinfunction "2_2") (pintype "passive"))
      (node (ref "U$5") (pin "AA2") (pinfunction "1_AA2") (pintype "bidirectional"))
      (node (ref "U$5") (pin "BA2") (pinfunction "1_BA2") (pintype "bidirectional"))
    )
    (net (code "82") (name "unconnected-(E1A-PRE-Pad4)") (class "Default")
      (node (ref "E1") (pin "4") (pinfunction "PRE_4") (pintype "input"))
    )
    (net (code "83") (name "unconnected-(E1A-~{Q}-Pad6)") (class "Default")
      (node (ref "E1") (pin "6") (pinfunction "~{Q}_6") (pintype "output"))
    )
    (net (code "84") (name "unconnected-(E1B-PRE-Pad10)") (class "Default")
      (node (ref "E1") (pin "10") (pinfunction "PRE_10") (pintype "input"))
    )
    (net (code "85") (name "unconnected-(E1B-~{Q}-Pad8)") (class "Default")
      (node (ref "E1") (pin "8") (pinfunction "~{Q}_8") (pintype "output"))
    )
    (net (code "86") (name "unconnected-(E2A-PRE-Pad4)") (class "Default")
      (node (ref "E2") (pin "4") (pinfunction "PRE_4") (pintype "input"))
    )
    (net (code "87") (name "unconnected-(E2A-~{Q}-Pad6)") (class "Default")
      (node (ref "E2") (pin "6") (pinfunction "~{Q}_6") (pintype "output"))
    )
    (net (code "88") (name "unconnected-(E2B-PRE-Pad10)") (class "Default")
      (node (ref "E2") (pin "10") (pinfunction "PRE_10") (pintype "input"))
    )
    (net (code "89") (name "unconnected-(E2B-~{Q}-Pad8)") (class "Default")
      (node (ref "E2") (pin "8") (pinfunction "~{Q}_8") (pintype "output"))
    )
    (net (code "90") (name "unconnected-(E3A-PRE-Pad4)") (class "Default")
      (node (ref "E3") (pin "4") (pinfunction "PRE_4") (pintype "input"))
    )
    (net (code "91") (name "unconnected-(E3A-~{Q}-Pad6)") (class "Default")
      (node (ref "E3") (pin "6") (pinfunction "~{Q}_6") (pintype "output"))
    )
    (net (code "92") (name "unconnected-(E3B-PRE-Pad10)") (class "Default")
      (node (ref "E3") (pin "10") (pinfunction "PRE_10") (pintype "input"))
    )
    (net (code "93") (name "unconnected-(E3B-~{Q}-Pad8)") (class "Default")
      (node (ref "E3") (pin "8") (pinfunction "~{Q}_8") (pintype "output"))
    )
    (net (code "94") (name "unconnected-(E4A-PRE-Pad4)") (class "Default")
      (node (ref "E4") (pin "4") (pinfunction "PRE_4") (pintype "input"))
    )
    (net (code "95") (name "unconnected-(E4A-~{Q}-Pad6)") (class "Default")
      (node (ref "E4") (pin "6") (pinfunction "~{Q}_6") (pintype "output"))
    )
    (net (code "96") (name "unconnected-(E4B-PRE-Pad10)") (class "Default")
      (node (ref "E4") (pin "10") (pinfunction "PRE_10") (pintype "input"))
    )
    (net (code "97") (name "unconnected-(E4B-~{Q}-Pad8)") (class "Default")
      (node (ref "E4") (pin "8") (pinfunction "~{Q}_8") (pintype "output"))
    )
    (net (code "98") (name "unconnected-(E10A-PRE-Pad4)") (class "Default")
      (node (ref "E10") (pin "4") (pinfunction "PRE_4") (pintype "input"))
    )
    (net (code "99") (name "unconnected-(E10A-~{Q}-Pad6)") (class "Default")
      (node (ref "E10") (pin "6") (pinfunction "~{Q}_6") (pintype "output"))
    )
    (net (code "100") (name "unconnected-(E14A-Q-Pad5)") (class "Default")
      (node (ref "E14") (pin "5") (pinfunction "Q_5") (pintype "output"))
    )
    (net (code "101") (name "unconnected-(E14B-Q-Pad9)") (class "Default")
      (node (ref "E14") (pin "9") (pinfunction "Q_9") (pintype "output"))
    )
    (net (code "102") (name "unconnected-(E18A-CLR-Pad1)") (class "Default")
      (node (ref "E18") (pin "1") (pinfunction "CLR_1") (pintype "input"))
    )
    (net (code "103") (name "unconnected-(E18A-PRE-Pad4)") (class "Default")
      (node (ref "E18") (pin "4") (pinfunction "PRE_4") (pintype "input"))
    )
    (net (code "104") (name "unconnected-(E18B-CLR-Pad13)") (class "Default")
      (node (ref "E18") (pin "13") (pinfunction "CLR_13") (pintype "input"))
    )
    (net (code "105") (name "unconnected-(E18B-PRE-Pad10)") (class "Default")
      (node (ref "E18") (pin "10") (pinfunction "PRE_10") (pintype "input"))
    )
  )
)
